# MCU.net
KiCad netlist of a schematic drawn in Altium Designer
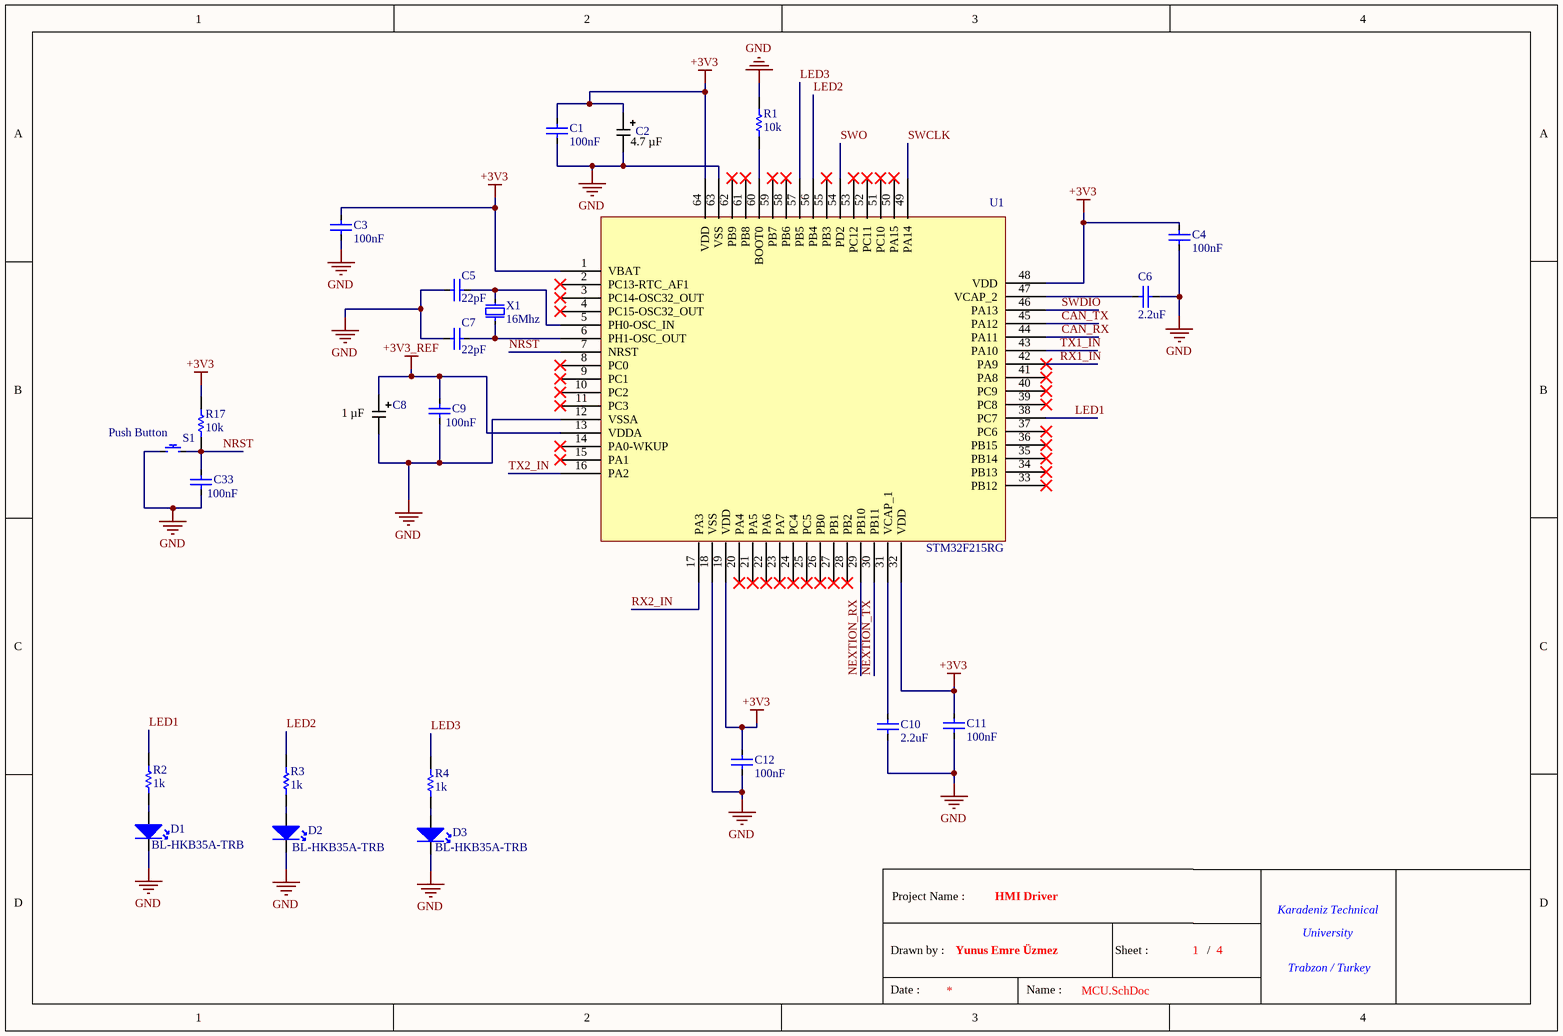
[diagram p0: MCU.SchDoc]

(export (version "E")
  (design (tool "Eeschema 10.0.6"))
  (components
    (comp (ref "C1")
      (value "100nF")
      (footprint "CAP-0603")
      (fields
        (field (name "MANUFACTURER") "TDK")
        (field (name "VOLTAGE") "50V")
        (field (name "TOLERANCE") "%10")
      )
      (libsource (lib "Motor_Driver") (part "CGA3E2X7R1H104K080AA"))
    )
    (comp (ref "C2")
      (value "T491B475K016AT")
      (footprint "KEMET_CAP_TAN-B")
      (description "CAP TANT 4.7UF 10% 16V 1411")
      (fields
        (field (name "MANUFACTURER") "KEMET")
        (field (name "TOLERANCE") "±10%")
        (field (name "CAPACITANCE") "4.7 µF")
      )
      (libsource (lib "Tantalum Capacitors") (part "T491B475K016AT"))
    )
    (comp (ref "C3")
      (value "100nF")
      (footprint "CAP-0603")
      (fields
        (field (name "MANUFACTURER") "TDK")
        (field (name "VOLTAGE") "50V")
        (field (name "TOLERANCE") "%10")
      )
      (libsource (lib "Motor_Driver") (part "CGA3E2X7R1H104K080AA"))
    )
    (comp (ref "C4")
      (value "100nF")
      (footprint "CAP-0603")
      (fields
        (field (name "MANUFACTURER") "TDK")
        (field (name "VOLTAGE") "50V")
        (field (name "TOLERANCE") "%10")
      )
      (libsource (lib "Motor_Driver") (part "CGA3E2X7R1H104K080AA"))
    )
    (comp (ref "C5")
      (value "22pF")
      (footprint "Motor_Driver:CAP-0805")
      (fields
        (field (name "MANUFACTURER") "Samsung Electro-Mechanics")
        (field (name "VOLTAGE") "50V")
        (field (name "TOLERANCE") "%5")
      )
      (libsource (lib "My_Libs") (part "CL21C220JBANNNC"))
    )
    (comp (ref "C6")
      (value "2.2uF")
      (footprint "CAP-0805")
      (fields
        (field (name "MANUFACTURER") "Samsung Electro-Mechanics")
        (field (name "TOLERANCE") "%10")
        (field (name "VOLTAGE") "25V")
      )
      (libsource (lib "Motor_Driver") (part "CL21B225KAFVPNE_1"))
    )
    (comp (ref "C7")
      (value "22pF")
      (footprint "Motor_Driver:CAP-0805")
      (fields
        (field (name "MANUFACTURER") "Samsung Electro-Mechanics")
        (field (name "VOLTAGE") "50V")
        (field (name "TOLERANCE") "%5")
      )
      (libsource (lib "My_Libs") (part "CL21C220JBANNNC"))
    )
    (comp (ref "C8")
      (value "T491B105K025AT")
      (footprint "KEMET_CAP_TAN-B")
      (description "CAP TANT 1UF 10% 25V 1411")
      (fields
        (field (name "MANUFACTURER") "KEMET")
        (field (name "TOLERANCE") "±10%")
        (field (name "CAPACITANCE") "1 µF")
      )
      (libsource (lib "Tantalum Capacitors") (part "T491B105K025AT"))
    )
    (comp (ref "C9")
      (value "100nF")
      (footprint "CAP-0603")
      (fields
        (field (name "MANUFACTURER") "TDK")
        (field (name "VOLTAGE") "50V")
        (field (name "TOLERANCE") "%10")
      )
      (libsource (lib "Motor_Driver") (part "CGA3E2X7R1H104K080AA"))
    )
    (comp (ref "C10")
      (value "2.2uF")
      (footprint "CAP-0805")
      (fields
        (field (name "MANUFACTURER") "Samsung Electro-Mechanics")
        (field (name "TOLERANCE") "%10")
        (field (name "VOLTAGE") "25V")
      )
      (libsource (lib "Motor_Driver") (part "CL21B225KAFVPNE_1"))
    )
    (comp (ref "C11")
      (value "100nF")
      (footprint "CAP-0603")
      (fields
        (field (name "MANUFACTURER") "TDK")
        (field (name "VOLTAGE") "50V")
        (field (name "TOLERANCE") "%10")
      )
      (libsource (lib "Motor_Driver") (part "CGA3E2X7R1H104K080AA"))
    )
    (comp (ref "C12")
      (value "100nF")
      (footprint "CAP-0603")
      (fields
        (field (name "MANUFACTURER") "TDK")
        (field (name "VOLTAGE") "50V")
        (field (name "TOLERANCE") "%10")
      )
      (libsource (lib "Motor_Driver") (part "CGA3E2X7R1H104K080AA"))
    )
    (comp (ref "C33")
      (value "100nF")
      (footprint "CAP-0603")
      (fields
        (field (name "MANUFACTURER") "TDK")
        (field (name "VOLTAGE") "50V")
        (field (name "TOLERANCE") "%10")
      )
      (libsource (lib "Motor_Driver") (part "CGA3E2X7R1H104K080AA"))
    )
    (comp (ref "D1")
      (value "BL-HKB35A-TRB")
      (footprint "LED-0805")
      (fields (field (name "MANUFACTURER") "BRIGHT LED"))
      (libsource (lib "Motor_Driver") (part "BL-HKB35A-TRB"))
    )
    (comp (ref "D2")
      (value "BL-HKB35A-TRB")
      (footprint "LED-0805")
      (fields (field (name "MANUFACTURER") "BRIGHT LED"))
      (libsource (lib "Motor_Driver") (part "BL-HKB35A-TRB"))
    )
    (comp (ref "D3")
      (value "BL-HKB35A-TRB")
      (footprint "LED-0805")
      (fields (field (name "MANUFACTURER") "BRIGHT LED"))
      (libsource (lib "Motor_Driver") (part "BL-HKB35A-TRB"))
    )
    (comp (ref "R1")
      (value "10k")
      (footprint "Motor_Driver:RES-0603")
      (fields
        (field (name "MANUFACTURER") "Vishay")
        (field (name "TOLERANCE") "%1")
        (field (name "POWER") "0.1W")
      )
      (libsource (lib "My_Libs") (part "CRCW060310K0FKEA"))
    )
    (comp (ref "R2")
      (value "1k")
      (footprint "Motor_Driver:RES-0603")
      (fields
        (field (name "MANUFACTURER") "Vishay")
        (field (name "TOLERANCE") "%1")
        (field (name "POWER") "0.1W")
      )
      (libsource (lib "My_Libs") (part "CRCW06031K00FKEAC"))
    )
    (comp (ref "R3")
      (value "1k")
      (footprint "Motor_Driver:RES-0603")
      (fields
        (field (name "MANUFACTURER") "Vishay")
        (field (name "TOLERANCE") "%1")
        (field (name "POWER") "0.1W")
      )
      (libsource (lib "My_Libs") (part "CRCW06031K00FKEAC"))
    )
    (comp (ref "R4")
      (value "1k")
      (footprint "Motor_Driver:RES-0603")
      (fields
        (field (name "MANUFACTURER") "Vishay")
        (field (name "TOLERANCE") "%1")
        (field (name "POWER") "0.1W")
      )
      (libsource (lib "My_Libs") (part "CRCW06031K00FKEAC"))
    )
    (comp (ref "R17")
      (value "10k")
      (footprint "Motor_Driver:RES-0603")
      (fields
        (field (name "MANUFACTURER") "Vishay")
        (field (name "TOLERANCE") "%1")
        (field (name "POWER") "0.1W")
      )
      (libsource (lib "My_Libs") (part "CRCW060310K0FKEA"))
    )
    (comp (ref "S1")
      (value "Push Button")
      (footprint "2.54mm_Push Button")
      (libsource (lib "Motor_Driver") (part "Push Button"))
    )
    (comp (ref "U1")
      (value "STM32F215RG")
      (footprint "LQFP64")
      (fields (field (name "MANUFACTURER") "STM"))
      (libsource (lib "jl_lib") (part "STM32F215RG"))
    )
    (comp (ref "X1")
      (value "16Mhz")
      (footprint "Motor_Driver:OSC-THT (11.5*5.00*3.60)")
      (fields (field (name "MANUFACTURER") "ANSEN"))
      (libsource (lib "My_Libs") (part "AS49S-16M-FC160F3"))
    )
  )
  (nets
    (net (code "1") (name "+3V3") (class "Default")
      (node (ref "C1") (pin "2") (pinfunction "2_2") (pintype "passive"))
      (node (ref "C11") (pin "2") (pinfunction "2_2") (pintype "passive"))
      (node (ref "C12") (pin "2") (pinfunction "2_2") (pintype "passive"))
      (node (ref "C2") (pin "1") (pinfunction "1_1") (pintype "passive"))
      (node (ref "C3") (pin "2") (pinfunction "2_2") (pintype "passive"))
      (node (ref "C4") (pin "2") (pinfunction "2_2") (pintype "passive"))
      (node (ref "R17") (pin "1") (pinfunction "1_1") (pintype "passive"))
      (node (ref "U1") (pin "1") (pinfunction "VBAT_1") (pintype "passive"))
      (node (ref "U1") (pin "19") (pinfunction "VDD_19") (pintype "passive"))
      (node (ref "U1") (pin "32") (pinfunction "VDD_32") (pintype "passive"))
      (node (ref "U1") (pin "48") (pinfunction "VDD_48") (pintype "passive"))
      (node (ref "U1") (pin "64") (pinfunction "VDD_64") (pintype "passive"))
    )
    (net (code "2") (name "+3V3_REF") (class "Default")
      (node (ref "C8") (pin "1") (pinfunction "1_1") (pintype "passive"))
      (node (ref "C9") (pin "2") (pinfunction "2_2") (pintype "passive"))
      (node (ref "U1") (pin "13") (pinfunction "VDDA_13") (pintype "passive"))
    )
    (net (code "3") (name "/CAN_RX") (class "Default")
      (node (ref "U1") (pin "44") (pinfunction "PA11_44") (pintype "passive"))
    )
    (net (code "4") (name "/CAN_TX") (class "Default")
      (node (ref "U1") (pin "45") (pinfunction "PA12_45") (pintype "passive"))
    )
    (net (code "5") (name "/LED1") (class "Default")
      (node (ref "R2") (pin "1") (pinfunction "1_1") (pintype "passive"))
      (node (ref "U1") (pin "38") (pinfunction "PC7_38") (pintype "passive"))
    )
    (net (code "6") (name "/LED2") (class "Default")
      (node (ref "R3") (pin "1") (pinfunction "1_1") (pintype "passive"))
      (node (ref "U1") (pin "56") (pinfunction "PB4_56") (pintype "passive"))
    )
    (net (code "7") (name "/LED3") (class "Default")
      (node (ref "R4") (pin "1") (pinfunction "1_1") (pintype "passive"))
      (node (ref "U1") (pin "57") (pinfunction "PB5_57") (pintype "passive"))
    )
    (net (code "8") (name "/NEXTION_RX") (class "Default")
      (node (ref "U1") (pin "29") (pinfunction "PB10_29") (pintype "passive"))
    )
    (net (code "9") (name "/NEXTION_TX") (class "Default")
      (node (ref "U1") (pin "30") (pinfunction "PB11_30") (pintype "passive"))
    )
    (net (code "10") (name "/NRST") (class "Default")
      (node (ref "C33") (pin "2") (pinfunction "2_2") (pintype "passive"))
      (node (ref "R17") (pin "2") (pinfunction "2_2") (pintype "passive"))
      (node (ref "S1") (pin "2") (pinfunction "2_2") (pintype "passive"))
      (node (ref "U1") (pin "7") (pinfunction "NRST_7") (pintype "passive"))
    )
    (net (code "11") (name "/RX1_IN") (class "Default")
      (node (ref "U1") (pin "42") (pinfunction "PA9_42") (pintype "passive+no_connect"))
    )
    (net (code "12") (name "/RX2_IN") (class "Default")
      (node (ref "U1") (pin "17") (pinfunction "PA3_17") (pintype "passive"))
    )
    (net (code "13") (name "/SWCLK") (class "Default")
      (node (ref "U1") (pin "49") (pinfunction "PA14_49") (pintype "passive"))
    )
    (net (code "14") (name "/SWDIO") (class "Default")
      (node (ref "U1") (pin "46") (pinfunction "PA13_46") (pintype "passive"))
    )
    (net (code "15") (name "/SWO") (class "Default")
      (node (ref "U1") (pin "54") (pinfunction "PD2_54") (pintype "passive"))
    )
    (net (code "16") (name "/TX1_IN") (class "Default")
      (node (ref "U1") (pin "43") (pinfunction "PA10_43") (pintype "passive"))
    )
    (net (code "17") (name "/TX2_IN") (class "Default")
      (node (ref "U1") (pin "16") (pinfunction "PA2_16") (pintype "passive"))
    )
    (net (code "18") (name "GND") (class "Default")
      (node (ref "C1") (pin "1") (pinfunction "1_1") (pintype "passive"))
      (node (ref "C10") (pin "1") (pinfunction "1_1") (pintype "passive"))
      (node (ref "C11") (pin "1") (pinfunction "1_1") (pintype "passive"))
      (node (ref "C12") (pin "1") (pinfunction "1_1") (pintype "passive"))
      (node (ref "C2") (pin "2") (pinfunction "2_2") (pintype "passive"))
      (node (ref "C3") (pin "1") (pinfunction "1_1") (pintype "passive"))
      (node (ref "C33") (pin "1") (pinfunction "1_1") (pintype "passive"))
      (node (ref "C4") (pin "1") (pinfunction "1_1") (pintype "passive"))
      (node (ref "C5") (pin "2") (pinfunction "2_2") (pintype "passive"))
      (node (ref "C6") (pin "1") (pinfunction "1_1") (pintype "passive"))
      (node (ref "C7") (pin "1") (pinfunction "1_1") (pintype "passive"))
      (node (ref "C8") (pin "2") (pinfunction "2_2") (pintype "passive"))
      (node (ref "C9") (pin "1") (pinfunction "1_1") (pintype "passive"))
      (node (ref "D1") (pin "2") (pinfunction "K_2") (pintype "passive"))
      (node (ref "D2") (pin "2") (pinfunction "K_2") (pintype "passive"))
      (node (ref "D3") (pin "2") (pinfunction "K_2") (pintype "passive"))
      (node (ref "R1") (pin "2") (pinfunction "2_2") (pintype "passive"))
      (node (ref "S1") (pin "1") (pinfunction "1_1") (pintype "passive"))
      (node (ref "U1") (pin "12") (pinfunction "VSSA_12") (pintype "passive"))
      (node (ref "U1") (pin "18") (pinfunction "VSS_18") (pintype "passive"))
      (node (ref "U1") (pin "63") (pinfunction "VSS_63") (pintype "passive"))
    )
    (net (code "19") (name "Net-(D1-A)") (class "Default")
      (node (ref "D1") (pin "1") (pinfunction "A_1") (pintype "passive"))
      (node (ref "R2") (pin "2") (pinfunction "2_2") (pintype "passive"))
    )
    (net (code "20") (name "Net-(D2-A)") (class "Default")
      (node (ref "D2") (pin "1") (pinfunction "A_1") (pintype "passive"))
      (node (ref "R3") (pin "2") (pinfunction "2_2") (pintype "passive"))
    )
    (net (code "21") (name "Net-(D3-A)") (class "Default")
      (node (ref "D3") (pin "1") (pinfunction "A_1") (pintype "passive"))
      (node (ref "R4") (pin "2") (pinfunction "2_2") (pintype "passive"))
    )
    (net (code "22") (name "Net-(U1-BOOT0)") (class "Default")
      (node (ref "R1") (pin "1") (pinfunction "1_1") (pintype "passive"))
      (node (ref "U1") (pin "60") (pinfunction "BOOT0_60") (pintype "passive"))
    )
    (net (code "23") (name "Net-(U1-PH0-OSC_IN)") (class "Default")
      (node (ref "C5") (pin "1") (pinfunction "1_1") (pintype "passive"))
      (node (ref "U1") (pin "5") (pinfunction "PH0-OSC_IN_5") (pintype "passive"))
      (node (ref "X1") (pin "2") (pinfunction "2_2") (pintype "passive"))
    )
    (net (code "24") (name "Net-(U1-PH1-OSC_OUT)") (class "Default")
      (node (ref "C7") (pin "2") (pinfunction "2_2") (pintype "passive"))
      (node (ref "U1") (pin "6") (pinfunction "PH1-OSC_OUT_6") (pintype "passive"))
      (node (ref "X1") (pin "1") (pinfunction "1_1") (pintype "passive"))
    )
    (net (code "25") (name "Net-(U1-VCAP_1)") (class "Default")
      (node (ref "C10") (pin "2") (pinfunction "2_2") (pintype "passive"))
      (node (ref "U1") (pin "31") (pinfunction "VCAP_1_31") (pintype "passive"))
    )
    (net (code "26") (name "Net-(U1-VCAP_2)") (class "Default")
      (node (ref "C6") (pin "2") (pinfunction "2_2") (pintype "passive"))
      (node (ref "U1") (pin "47") (pinfunction "VCAP_2_47") (pintype "passive"))
    )
    (net (code "27") (name "unconnected-(U1-PA0-WKUP-Pad14)") (class "Default")
      (node (ref "U1") (pin "14") (pinfunction "PA0-WKUP_14") (pintype "passive+no_connect"))
    )
    (net (code "28") (name "unconnected-(U1-PA1-Pad15)") (class "Default")
      (node (ref "U1") (pin "15") (pinfunction "PA1_15") (pintype "passive+no_connect"))
    )
    (net (code "29") (name "unconnected-(U1-PA4-Pad20)") (class "Default")
      (node (ref "U1") (pin "20") (pinfunction "PA4_20") (pintype "passive+no_connect"))
    )
    (net (code "30") (name "unconnected-(U1-PA5-Pad21)") (class "Default")
      (node (ref "U1") (pin "21") (pinfunction "PA5_21") (pintype "passive+no_connect"))
    )
    (net (code "31") (name "unconnected-(U1-PA6-Pad22)") (class "Default")
      (node (ref "U1") (pin "22") (pinfunction "PA6_22") (pintype "passive+no_connect"))
    )
    (net (code "32") (name "unconnected-(U1-PA7-Pad23)") (class "Default")
      (node (ref "U1") (pin "23") (pinfunction "PA7_23") (pintype "passive+no_connect"))
    )
    (net (code "33") (name "unconnected-(U1-PA8-Pad41)") (class "Default")
      (node (ref "U1") (pin "41") (pinfunction "PA8_41") (pintype "passive+no_connect"))
    )
    (net (code "34") (name "unconnected-(U1-PA15-Pad50)") (class "Default")
      (node (ref "U1") (pin "50") (pinfunction "PA15_50") (pintype "passive+no_connect"))
    )
    (net (code "35") (name "unconnected-(U1-PB0-Pad26)") (class "Default")
      (node (ref "U1") (pin "26") (pinfunction "PB0_26") (pintype "passive+no_connect"))
    )
    (net (code "36") (name "unconnected-(U1-PB1-Pad27)") (class "Default")
      (node (ref "U1") (pin "27") (pinfunction "PB1_27") (pintype "passive+no_connect"))
    )
    (net (code "37") (name "unconnected-(U1-PB2-Pad28)") (class "Default")
      (node (ref "U1") (pin "28") (pinfunction "PB2_28") (pintype "passive+no_connect"))
    )
    (net (code "38") (name "unconnected-(U1-PB3-Pad55)") (class "Default")
      (node (ref "U1") (pin "55") (pinfunction "PB3_55") (pintype "passive+no_connect"))
    )
    (net (code "39") (name "unconnected-(U1-PB6-Pad58)") (class "Default")
      (node (ref "U1") (pin "58") (pinfunction "PB6_58") (pintype "passive+no_connect"))
    )
    (net (code "40") (name "unconnected-(U1-PB7-Pad59)") (class "Default")
      (node (ref "U1") (pin "59") (pinfunction "PB7_59") (pintype "passive+no_connect"))
    )
    (net (code "41") (name "unconnected-(U1-PB8-Pad61)") (class "Default")
      (node (ref "U1") (pin "61") (pinfunction "PB8_61") (pintype "passive+no_connect"))
    )
    (net (code "42") (name "unconnected-(U1-PB9-Pad62)") (class "Default")
      (node (ref "U1") (pin "62") (pinfunction "PB9_62") (pintype "passive+no_connect"))
    )
    (net (code "43") (name "unconnected-(U1-PB12-Pad33)") (class "Default")
      (node (ref "U1") (pin "33") (pinfunction "PB12_33") (pintype "passive+no_connect"))
    )
    (net (code "44") (name "unconnected-(U1-PB13-Pad34)") (class "Default")
      (node (ref "U1") (pin "34") (pinfunction "PB13_34") (pintype "passive+no_connect"))
    )
    (net (code "45") (name "unconnected-(U1-PB14-Pad35)") (class "Default")
      (node (ref "U1") (pin "35") (pinfunction "PB14_35") (pintype "passive+no_connect"))
    )
    (net (code "46") (name "unconnected-(U1-PB15-Pad36)") (class "Default")
      (node (ref "U1") (pin "36") (pinfunction "PB15_36") (pintype "passive+no_connect"))
    )
    (net (code "47") (name "unconnected-(U1-PC0-Pad8)") (class "Default")
      (node (ref "U1") (pin "8") (pinfunction "PC0_8") (pintype "passive+no_connect"))
    )
    (net (code "48") (name "unconnected-(U1-PC1-Pad9)") (class "Default")
      (node (ref "U1") (pin "9") (pinfunction "PC1_9") (pintype "passive+no_connect"))
    )
    (net (code "49") (name "unconnected-(U1-PC2-Pad10)") (class "Default")
      (node (ref "U1") (pin "10") (pinfunction "PC2_10") (pintype "passive+no_connect"))
    )
    (net (code "50") (name "unconnected-(U1-PC3-Pad11)") (class "Default")
      (node (ref "U1") (pin "11") (pinfunction "PC3_11") (pintype "passive+no_connect"))
    )
    (net (code "51") (name "unconnected-(U1-PC4-Pad24)") (class "Default")
      (node (ref "U1") (pin "24") (pinfunction "PC4_24") (pintype "passive+no_connect"))
    )
    (net (code "52") (name "unconnected-(U1-PC5-Pad25)") (class "Default")
      (node (ref "U1") (pin "25") (pinfunction "PC5_25") (pintype "passive+no_connect"))
    )
    (net (code "53") (name "unconnected-(U1-PC6-Pad37)") (class "Default")
      (node (ref "U1") (pin "37") (pinfunction "PC6_37") (pintype "passive+no_connect"))
    )
    (net (code "54") (name "unconnected-(U1-PC8-Pad39)") (class "Default")
      (node (ref "U1") (pin "39") (pinfunction "PC8_39") (pintype "passive+no_connect"))
    )
    (net (code "55") (name "unconnected-(U1-PC9-Pad40)") (class "Default")
      (node (ref "U1") (pin "40") (pinfunction "PC9_40") (pintype "passive+no_connect"))
    )
    (net (code "56") (name "unconnected-(U1-PC10-Pad51)") (class "Default")
      (node (ref "U1") (pin "51") (pinfunction "PC10_51") (pintype "passive+no_connect"))
    )
    (net (code "57") (name "unconnected-(U1-PC11-Pad52)") (class "Default")
      (node (ref "U1") (pin "52") (pinfunction "PC11_52") (pintype "passive+no_connect"))
    )
    (net (code "58") (name "unconnected-(U1-PC12-Pad53)") (class "Default")
      (node (ref "U1") (pin "53") (pinfunction "PC12_53") (pintype "passive+no_connect"))
    )
    (net (code "59") (name "unconnected-(U1-PC13-RTC_AF1-Pad2)") (class "Default")
      (node (ref "U1") (pin "2") (pinfunction "PC13-RTC_AF1_2") (pintype "passive+no_connect"))
    )
    (net (code "60") (name "unconnected-(U1-PC14-OSC32_OUT-Pad3)") (class "Default")
      (node (ref "U1") (pin "3") (pinfunction "PC14-OSC32_OUT_3") (pintype "passive+no_connect"))
    )
    (net (code "61") (name "unconnected-(U1-PC15-OSC32_OUT-Pad4)") (class "Default")
      (node (ref "U1") (pin "4") (pinfunction "PC15-OSC32_OUT_4") (pintype "passive+no_connect"))
    )
  )
)
